# Ethernet2.net
KiCad netlist of a schematic drawn in Altium Designer
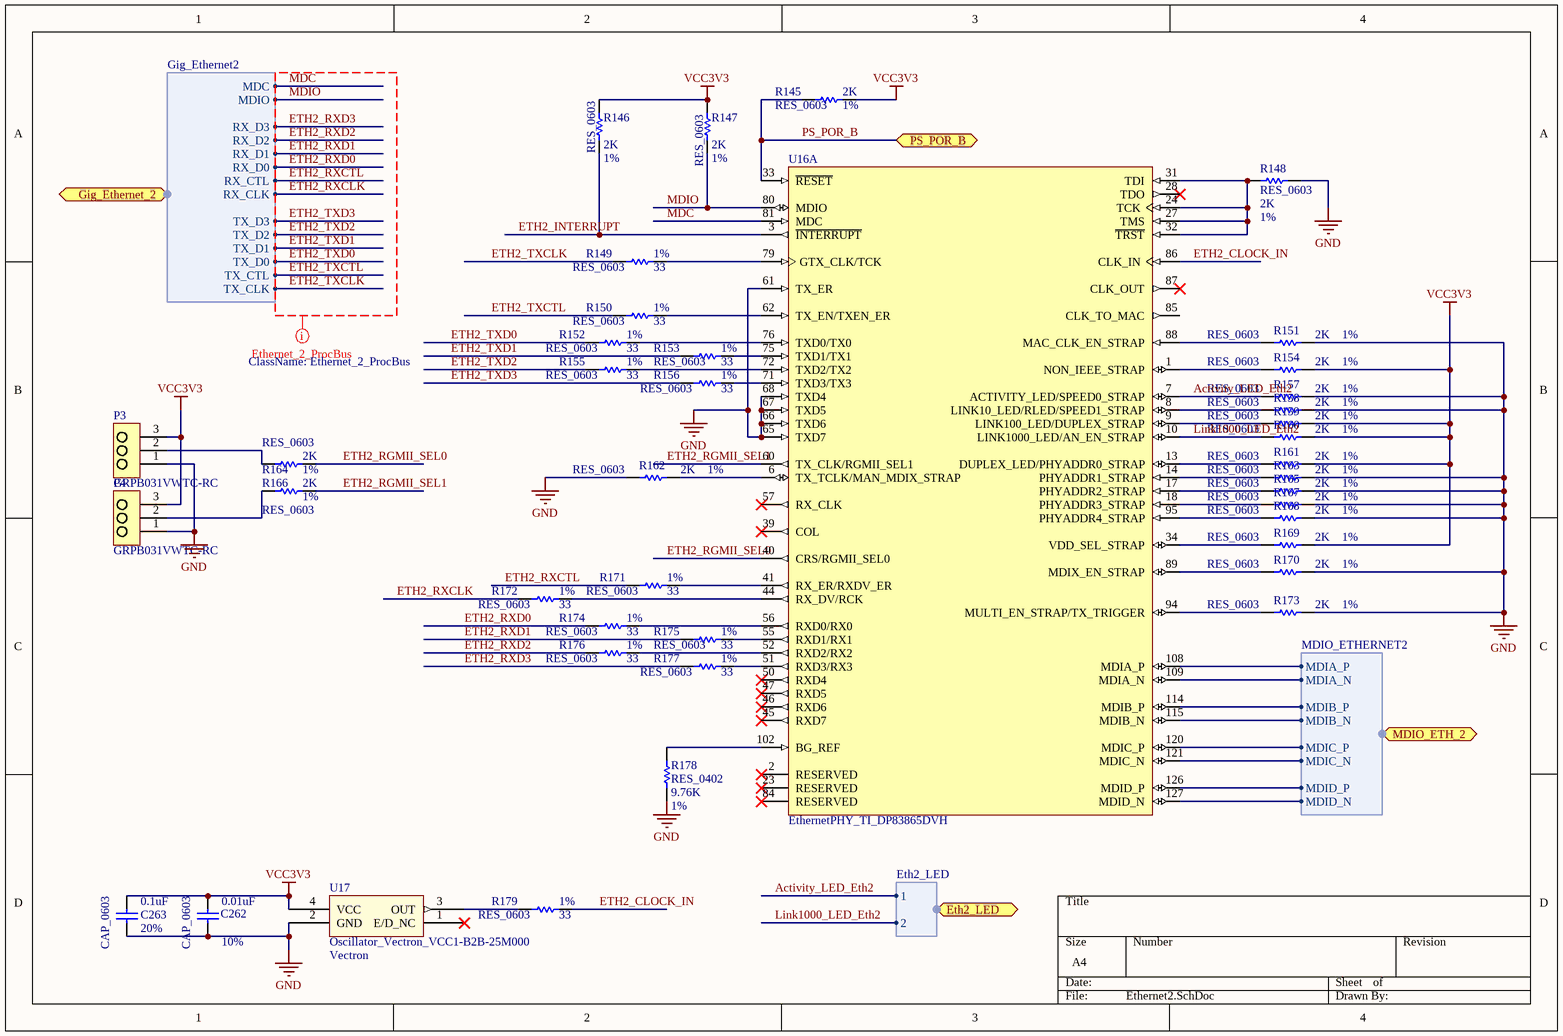
[diagram p0: Ethernet2.SchDoc]

(export (version "E")
  (design (tool "Eeschema 10.0.6"))
  (components
    (comp (ref "C262")
      (value "CAP_0603")
      (footprint "CAPC0603(1608)100_N")
      (description "CAP CER 10000PF 6.3V X7R 0603")
      (fields
        (field (name "ALTIUM_VALUE") "0.01uF")
        (field (name "TOLERANCE") "10%")
        (field (name "PART NUMBER") "C0603C103K9RACTU")
        (field (name "MANUFACTURER") "Kemet")
      )
      (libsource (lib "COMRAD_Database") (part "CAP_0603"))
    )
    (comp (ref "C263")
      (value "CAP_0603")
      (footprint "CAPC0603(1608)100_N")
      (description "CAP CER 0.1UF 6.3V 20% X7R 0603")
      (fields
        (field (name "ALTIUM_VALUE") "0.1uF")
        (field (name "TOLERANCE") "20%")
        (field (name "PART NUMBER") "6R3X14W104MV4T")
        (field (name "MANUFACTURER") "Johanson Dielectrics Inc")
      )
      (libsource (lib "COMRAD_Database") (part "CAP_0603"))
    )
    (comp (ref "P3")
      (value "GRPB031VWTC-RC")
      (footprint "Header_3-Pos_Sullins_GRPB031VWTC-RC")
      (description "CONN HEADER .050\" 3POS SMD GOLD")
      (fields (field (name "MANUFACTURER") "Sullins Connector Solutions"))
      (libsource (lib "COMRAD_Database") (part "Jumper_Header3"))
    )
    (comp (ref "P4")
      (value "GRPB031VWTC-RC")
      (footprint "Header_3-Pos_Sullins_GRPB031VWTC-RC")
      (description "CONN HEADER .050\" 3POS SMD GOLD")
      (fields (field (name "MANUFACTURER") "Sullins Connector Solutions"))
      (libsource (lib "COMRAD_Database") (part "Jumper_Header3"))
    )
    (comp (ref "R145")
      (value "RES_0603")
      (footprint "RESC0603(1608)_N")
      (description "RES 2.00K OHM 1/10W 1% 0603 SMD")
      (fields
        (field (name "ALTIUM_VALUE") "2K")
        (field (name "TOLERANCE") "1%")
        (field (name "PART NUMBER") "ERJ-3EKF2001V")
        (field (name "MANUFACTURER") "Panasonic Electronics Components")
      )
      (libsource (lib "COMRAD_Database") (part "RES_0603"))
    )
    (comp (ref "R146")
      (value "RES_0603")
      (footprint "RESC0603(1608)_N")
      (description "RES 2.00K OHM 1/10W 1% 0603 SMD")
      (fields
        (field (name "ALTIUM_VALUE") "2K")
        (field (name "TOLERANCE") "1%")
        (field (name "PART NUMBER") "ERJ-3EKF2001V")
        (field (name "MANUFACTURER") "Panasonic Electronics Components")
      )
      (libsource (lib "COMRAD_Database") (part "RES_0603"))
    )
    (comp (ref "R147")
      (value "RES_0603")
      (footprint "RESC0603(1608)_N")
      (description "RES 2.00K OHM 1/10W 1% 0603 SMD")
      (fields
        (field (name "ALTIUM_VALUE") "2K")
        (field (name "TOLERANCE") "1%")
        (field (name "PART NUMBER") "ERJ-3EKF2001V")
        (field (name "MANUFACTURER") "Panasonic Electronics Components")
      )
      (libsource (lib "COMRAD_Database") (part "RES_0603"))
    )
    (comp (ref "R148")
      (value "RES_0603")
      (footprint "RESC0603(1608)_N")
      (description "RES 2.00K OHM 1/10W 1% 0603 SMD")
      (fields
        (field (name "ALTIUM_VALUE") "2K")
        (field (name "TOLERANCE") "1%")
        (field (name "PART NUMBER") "ERJ-3EKF2001V")
        (field (name "MANUFACTURER") "Panasonic Electronics Components")
      )
      (libsource (lib "COMRAD_Database") (part "RES_0603"))
    )
    (comp (ref "R149")
      (value "RES_0603")
      (footprint "RESC0603(1608)_N")
      (description "RES 33.0 OHM 1/10W 1% 0603 SMD")
      (fields
        (field (name "ALTIUM_VALUE") "33")
        (field (name "TOLERANCE") "1%")
        (field (name "PART NUMBER") "ERJ-3EKF33R0V")
        (field (name "MANUFACTURER") "Panasonic Electronics Components")
      )
      (libsource (lib "COMRAD_Database") (part "RES_0603"))
    )
    (comp (ref "R150")
      (value "RES_0603")
      (footprint "RESC0603(1608)_N")
      (description "RES 33.0 OHM 1/10W 1% 0603 SMD")
      (fields
        (field (name "ALTIUM_VALUE") "33")
        (field (name "TOLERANCE") "1%")
        (field (name "PART NUMBER") "ERJ-3EKF33R0V")
        (field (name "MANUFACTURER") "Panasonic Electronics Components")
      )
      (libsource (lib "COMRAD_Database") (part "RES_0603"))
    )
    (comp (ref "R151")
      (value "RES_0603")
      (footprint "RESC0603(1608)_N")
      (description "RES 2.00K OHM 1/10W 1% 0603 SMD")
      (fields
        (field (name "ALTIUM_VALUE") "2K")
        (field (name "TOLERANCE") "1%")
        (field (name "PART NUMBER") "ERJ-3EKF2001V")
        (field (name "MANUFACTURER") "Panasonic Electronics Components")
      )
      (libsource (lib "COMRAD_Database") (part "RES_0603"))
    )
    (comp (ref "R152")
      (value "RES_0603")
      (footprint "RESC0603(1608)_N")
      (description "RES 33.0 OHM 1/10W 1% 0603 SMD")
      (fields
        (field (name "ALTIUM_VALUE") "33")
        (field (name "TOLERANCE") "1%")
        (field (name "PART NUMBER") "ERJ-3EKF33R0V")
        (field (name "MANUFACTURER") "Panasonic Electronics Components")
      )
      (libsource (lib "COMRAD_Database") (part "RES_0603"))
    )
    (comp (ref "R153")
      (value "RES_0603")
      (footprint "RESC0603(1608)_N")
      (description "RES 33.0 OHM 1/10W 1% 0603 SMD")
      (fields
        (field (name "ALTIUM_VALUE") "33")
        (field (name "TOLERANCE") "1%")
        (field (name "PART NUMBER") "ERJ-3EKF33R0V")
        (field (name "MANUFACTURER") "Panasonic Electronics Components")
      )
      (libsource (lib "COMRAD_Database") (part "RES_0603"))
    )
    (comp (ref "R154")
      (value "RES_0603")
      (footprint "RESC0603(1608)_N")
      (description "RES 2.00K OHM 1/10W 1% 0603 SMD")
      (fields
        (field (name "ALTIUM_VALUE") "2K")
        (field (name "TOLERANCE") "1%")
        (field (name "PART NUMBER") "ERJ-3EKF2001V")
        (field (name "MANUFACTURER") "Panasonic Electronics Components")
      )
      (libsource (lib "COMRAD_Database") (part "RES_0603"))
    )
    (comp (ref "R155")
      (value "RES_0603")
      (footprint "RESC0603(1608)_N")
      (description "RES 33.0 OHM 1/10W 1% 0603 SMD")
      (fields
        (field (name "ALTIUM_VALUE") "33")
        (field (name "TOLERANCE") "1%")
        (field (name "PART NUMBER") "ERJ-3EKF33R0V")
        (field (name "MANUFACTURER") "Panasonic Electronics Components")
      )
      (libsource (lib "COMRAD_Database") (part "RES_0603"))
    )
    (comp (ref "R156")
      (value "RES_0603")
      (footprint "RESC0603(1608)_N")
      (description "RES 33.0 OHM 1/10W 1% 0603 SMD")
      (fields
        (field (name "ALTIUM_VALUE") "33")
        (field (name "TOLERANCE") "1%")
        (field (name "PART NUMBER") "ERJ-3EKF33R0V")
        (field (name "MANUFACTURER") "Panasonic Electronics Components")
      )
      (libsource (lib "COMRAD_Database") (part "RES_0603"))
    )
    (comp (ref "R157")
      (value "RES_0603")
      (footprint "RESC0603(1608)_N")
      (description "RES 2.00K OHM 1/10W 1% 0603 SMD")
      (fields
        (field (name "ALTIUM_VALUE") "2K")
        (field (name "TOLERANCE") "1%")
        (field (name "PART NUMBER") "ERJ-3EKF2001V")
        (field (name "MANUFACTURER") "Panasonic Electronics Components")
      )
      (libsource (lib "COMRAD_Database") (part "RES_0603"))
    )
    (comp (ref "R158")
      (value "RES_0603")
      (footprint "RESC0603(1608)_N")
      (description "RES 2.00K OHM 1/10W 1% 0603 SMD")
      (fields
        (field (name "ALTIUM_VALUE") "2K")
        (field (name "TOLERANCE") "1%")
        (field (name "PART NUMBER") "ERJ-3EKF2001V")
        (field (name "MANUFACTURER") "Panasonic Electronics Components")
      )
      (libsource (lib "COMRAD_Database") (part "RES_0603"))
    )
    (comp (ref "R159")
      (value "RES_0603")
      (footprint "RESC0603(1608)_N")
      (description "RES 2.00K OHM 1/10W 1% 0603 SMD")
      (fields
        (field (name "ALTIUM_VALUE") "2K")
        (field (name "TOLERANCE") "1%")
        (field (name "PART NUMBER") "ERJ-3EKF2001V")
        (field (name "MANUFACTURER") "Panasonic Electronics Components")
      )
      (libsource (lib "COMRAD_Database") (part "RES_0603"))
    )
    (comp (ref "R160")
      (value "RES_0603")
      (footprint "RESC0603(1608)_N")
      (description "RES 2.00K OHM 1/10W 1% 0603 SMD")
      (fields
        (field (name "ALTIUM_VALUE") "2K")
        (field (name "TOLERANCE") "1%")
        (field (name "PART NUMBER") "ERJ-3EKF2001V")
        (field (name "MANUFACTURER") "Panasonic Electronics Components")
      )
      (libsource (lib "COMRAD_Database") (part "RES_0603"))
    )
    (comp (ref "R161")
      (value "RES_0603")
      (footprint "RESC0603(1608)_N")
      (description "RES 2.00K OHM 1/10W 1% 0603 SMD")
      (fields
        (field (name "ALTIUM_VALUE") "2K")
        (field (name "TOLERANCE") "1%")
        (field (name "PART NUMBER") "ERJ-3EKF2001V")
        (field (name "MANUFACTURER") "Panasonic Electronics Components")
      )
      (libsource (lib "COMRAD_Database") (part "RES_0603"))
    )
    (comp (ref "R162")
      (value "RES_0603")
      (footprint "RESC0603(1608)_N")
      (description "RES 2.00K OHM 1/10W 1% 0603 SMD")
      (fields
        (field (name "ALTIUM_VALUE") "2K")
        (field (name "TOLERANCE") "1%")
        (field (name "PART NUMBER") "ERJ-3EKF2001V")
        (field (name "MANUFACTURER") "Panasonic Electronics Components")
      )
      (libsource (lib "COMRAD_Database") (part "RES_0603"))
    )
    (comp (ref "R163")
      (value "RES_0603")
      (footprint "RESC0603(1608)_N")
      (description "RES 2.00K OHM 1/10W 1% 0603 SMD")
      (fields
        (field (name "ALTIUM_VALUE") "2K")
        (field (name "TOLERANCE") "1%")
        (field (name "PART NUMBER") "ERJ-3EKF2001V")
        (field (name "MANUFACTURER") "Panasonic Electronics Components")
      )
      (libsource (lib "COMRAD_Database") (part "RES_0603"))
    )
    (comp (ref "R164")
      (value "RES_0603")
      (footprint "RESC0603(1608)_N")
      (description "RES 2.00K OHM 1/10W 1% 0603 SMD")
      (fields
        (field (name "ALTIUM_VALUE") "2K")
        (field (name "TOLERANCE") "1%")
        (field (name "PART NUMBER") "ERJ-3EKF2001V")
        (field (name "MANUFACTURER") "Panasonic Electronics Components")
      )
      (libsource (lib "COMRAD_Database") (part "RES_0603"))
    )
    (comp (ref "R165")
      (value "RES_0603")
      (footprint "RESC0603(1608)_N")
      (description "RES 2.00K OHM 1/10W 1% 0603 SMD")
      (fields
        (field (name "ALTIUM_VALUE") "2K")
        (field (name "TOLERANCE") "1%")
        (field (name "PART NUMBER") "ERJ-3EKF2001V")
        (field (name "MANUFACTURER") "Panasonic Electronics Components")
      )
      (libsource (lib "COMRAD_Database") (part "RES_0603"))
    )
    (comp (ref "R166")
      (value "RES_0603")
      (footprint "RESC0603(1608)_N")
      (description "RES 2.00K OHM 1/10W 1% 0603 SMD")
      (fields
        (field (name "ALTIUM_VALUE") "2K")
        (field (name "TOLERANCE") "1%")
        (field (name "PART NUMBER") "ERJ-3EKF2001V")
        (field (name "MANUFACTURER") "Panasonic Electronics Components")
      )
      (libsource (lib "COMRAD_Database") (part "RES_0603"))
    )
    (comp (ref "R167")
      (value "RES_0603")
      (footprint "RESC0603(1608)_N")
      (description "RES 2.00K OHM 1/10W 1% 0603 SMD")
      (fields
        (field (name "ALTIUM_VALUE") "2K")
        (field (name "TOLERANCE") "1%")
        (field (name "PART NUMBER") "ERJ-3EKF2001V")
        (field (name "MANUFACTURER") "Panasonic Electronics Components")
      )
      (libsource (lib "COMRAD_Database") (part "RES_0603"))
    )
    (comp (ref "R168")
      (value "RES_0603")
      (footprint "RESC0603(1608)_N")
      (description "RES 2.00K OHM 1/10W 1% 0603 SMD")
      (fields
        (field (name "ALTIUM_VALUE") "2K")
        (field (name "TOLERANCE") "1%")
        (field (name "PART NUMBER") "ERJ-3EKF2001V")
        (field (name "MANUFACTURER") "Panasonic Electronics Components")
      )
      (libsource (lib "COMRAD_Database") (part "RES_0603"))
    )
    (comp (ref "R169")
      (value "RES_0603")
      (footprint "RESC0603(1608)_N")
      (description "RES 2.00K OHM 1/10W 1% 0603 SMD")
      (fields
        (field (name "ALTIUM_VALUE") "2K")
        (field (name "TOLERANCE") "1%")
        (field (name "PART NUMBER") "ERJ-3EKF2001V")
        (field (name "MANUFACTURER") "Panasonic Electronics Components")
      )
      (libsource (lib "COMRAD_Database") (part "RES_0603"))
    )
    (comp (ref "R170")
      (value "RES_0603")
      (footprint "RESC0603(1608)_N")
      (description "RES 2.00K OHM 1/10W 1% 0603 SMD")
      (fields
        (field (name "ALTIUM_VALUE") "2K")
        (field (name "TOLERANCE") "1%")
        (field (name "PART NUMBER") "ERJ-3EKF2001V")
        (field (name "MANUFACTURER") "Panasonic Electronics Components")
      )
      (libsource (lib "COMRAD_Database") (part "RES_0603"))
    )
    (comp (ref "R171")
      (value "RES_0603")
      (footprint "RESC0603(1608)_N")
      (description "RES 33.0 OHM 1/10W 1% 0603 SMD")
      (fields
        (field (name "ALTIUM_VALUE") "33")
        (field (name "TOLERANCE") "1%")
        (field (name "PART NUMBER") "ERJ-3EKF33R0V")
        (field (name "MANUFACTURER") "Panasonic Electronics Components")
      )
      (libsource (lib "COMRAD_Database") (part "RES_0603"))
    )
    (comp (ref "R172")
      (value "RES_0603")
      (footprint "RESC0603(1608)_N")
      (description "RES 33.0 OHM 1/10W 1% 0603 SMD")
      (fields
        (field (name "ALTIUM_VALUE") "33")
        (field (name "TOLERANCE") "1%")
        (field (name "PART NUMBER") "ERJ-3EKF33R0V")
        (field (name "MANUFACTURER") "Panasonic Electronics Components")
      )
      (libsource (lib "COMRAD_Database") (part "RES_0603"))
    )
    (comp (ref "R173")
      (value "RES_0603")
      (footprint "RESC0603(1608)_N")
      (description "RES 2.00K OHM 1/10W 1% 0603 SMD")
      (fields
        (field (name "ALTIUM_VALUE") "2K")
        (field (name "TOLERANCE") "1%")
        (field (name "PART NUMBER") "ERJ-3EKF2001V")
        (field (name "MANUFACTURER") "Panasonic Electronics Components")
      )
      (libsource (lib "COMRAD_Database") (part "RES_0603"))
    )
    (comp (ref "R174")
      (value "RES_0603")
      (footprint "RESC0603(1608)_N")
      (description "RES 33.0 OHM 1/10W 1% 0603 SMD")
      (fields
        (field (name "ALTIUM_VALUE") "33")
        (field (name "TOLERANCE") "1%")
        (field (name "PART NUMBER") "ERJ-3EKF33R0V")
        (field (name "MANUFACTURER") "Panasonic Electronics Components")
      )
      (libsource (lib "COMRAD_Database") (part "RES_0603"))
    )
    (comp (ref "R175")
      (value "RES_0603")
      (footprint "RESC0603(1608)_N")
      (description "RES 33.0 OHM 1/10W 1% 0603 SMD")
      (fields
        (field (name "ALTIUM_VALUE") "33")
        (field (name "TOLERANCE") "1%")
        (field (name "PART NUMBER") "ERJ-3EKF33R0V")
        (field (name "MANUFACTURER") "Panasonic Electronics Components")
      )
      (libsource (lib "COMRAD_Database") (part "RES_0603"))
    )
    (comp (ref "R176")
      (value "RES_0603")
      (footprint "RESC0603(1608)_N")
      (description "RES 33.0 OHM 1/10W 1% 0603 SMD")
      (fields
        (field (name "ALTIUM_VALUE") "33")
        (field (name "TOLERANCE") "1%")
        (field (name "PART NUMBER") "ERJ-3EKF33R0V")
        (field (name "MANUFACTURER") "Panasonic Electronics Components")
      )
      (libsource (lib "COMRAD_Database") (part "RES_0603"))
    )
    (comp (ref "R177")
      (value "RES_0603")
      (footprint "RESC0603(1608)_N")
      (description "RES 33.0 OHM 1/10W 1% 0603 SMD")
      (fields
        (field (name "ALTIUM_VALUE") "33")
        (field (name "TOLERANCE") "1%")
        (field (name "PART NUMBER") "ERJ-3EKF33R0V")
        (field (name "MANUFACTURER") "Panasonic Electronics Components")
      )
      (libsource (lib "COMRAD_Database") (part "RES_0603"))
    )
    (comp (ref "R178")
      (value "RES_0402")
      (footprint "RESC0402(1005)_N")
      (description "9.76K ohm, 1% 1/16W, 0402")
      (fields
        (field (name "ALTIUM_VALUE") "9.76K")
        (field (name "TOLERANCE") "1%")
        (field (name "PART NUMBER") "CRCW04029K76FKED")
        (field (name "MANUFACTURER") "Vishay/Dale")
      )
      (libsource (lib "COMRAD_Database") (part "RES_0402"))
    )
    (comp (ref "R179")
      (value "RES_0603")
      (footprint "RESC0603(1608)_N")
      (description "RES 33.0 OHM 1/10W 1% 0603 SMD")
      (fields
        (field (name "ALTIUM_VALUE") "33")
        (field (name "TOLERANCE") "1%")
        (field (name "PART NUMBER") "ERJ-3EKF33R0V")
        (field (name "MANUFACTURER") "Panasonic Electronics Components")
      )
      (libsource (lib "COMRAD_Database") (part "RES_0603"))
    )
    (comp (ref "U16")
      (value "EthernetPHY_TI_DP83865DVH")
      (footprint "EthernetPHY_TI_DP83865(PQFP)_VLA128A_N")
      (description "Ethernet PHY_TI_DP83865DVH, Gigabit Ethernet PHYTER,128 Lead Plastic Flat Pack")
      (fields (field (name "PART NUMBER") "DP83865DVH") (field (name "MANUFACTURER") "Texas Instruments"))
      (libsource (lib "COMRAD_Database") (part "EthernetPHY_TI_DP83865DVH"))
    )
    (comp (ref "U17")
      (value "Oscillator_Vectron_VCC1-B2B-25M000")
      (footprint "Oscillator_Vectron_VCC1-B2B-25M000_SMD")
      (description "VCC1-B2B-25M000, 25MHz, 3.3V +/- 10%, No tri-state, +/-50 ppm, -40 to +85 deg")
      (fields (field (name "PART NUMBER") "VCC1-B2B-25M000") (field (name "MANUFACTURER") "Vectron"))
      (libsource (lib "COMRAD_Database") (part "Oscillator_Vectron_VCC1-B2B-25M000"))
    )
  )
  (nets
    (net (code "4") (name "/Activity_LED_Eth2") (class "Default")
      (node (ref "R157") (pin "2") (pinfunction "2_2") (pintype "passive"))
      (node (ref "U16") (pin "7") (pinfunction "ACTIVITY_LED/SPEED0_STRAP_7") (pintype "bidirectional"))
    )
    (net (code "5") (name "/ETH2_CLOCK_IN") (class "Default")
      (node (ref "R179") (pin "2") (pinfunction "2_2") (pintype "passive"))
      (node (ref "U16") (pin "86") (pinfunction "CLK_IN_86") (pintype "input"))
    )
    (net (code "6") (name "/ETH2_INTERRUPT") (class "Default")
      (node (ref "R146") (pin "1") (pinfunction "1_1") (pintype "passive"))
      (node (ref "U16") (pin "3") (pinfunction "~{INTERRUPT}_3") (pintype "output"))
    )
    (net (code "7") (name "/ETH2_RGMII_SEL0") (class "Default")
      (node (ref "R164") (pin "1") (pinfunction "1_1") (pintype "passive"))
      (node (ref "U16") (pin "40") (pinfunction "CRS/RGMII_SEL0_40") (pintype "output"))
    )
    (net (code "8") (name "/ETH2_RGMII_SEL1") (class "Default")
      (node (ref "R166") (pin "1") (pinfunction "1_1") (pintype "passive"))
      (node (ref "U16") (pin "60") (pinfunction "TX_CLK/RGMII_SEL1_60") (pintype "output"))
    )
    (net (code "9") (name "/ETH2_RXCLK") (class "Default")
      (node (ref "R172") (pin "1") (pinfunction "1_1") (pintype "passive"))
    )
    (net (code "10") (name "/ETH2_RXCTL") (class "Default")
      (node (ref "R171") (pin "1") (pinfunction "1_1") (pintype "passive"))
    )
    (net (code "11") (name "/ETH2_RXD0") (class "Default")
      (node (ref "R174") (pin "1") (pinfunction "1_1") (pintype "passive"))
    )
    (net (code "12") (name "/ETH2_RXD1") (class "Default")
      (node (ref "R175") (pin "1") (pinfunction "1_1") (pintype "passive"))
    )
    (net (code "13") (name "/ETH2_RXD2") (class "Default")
      (node (ref "R176") (pin "1") (pinfunction "1_1") (pintype "passive"))
    )
    (net (code "14") (name "/ETH2_RXD3") (class "Default")
      (node (ref "R177") (pin "1") (pinfunction "1_1") (pintype "passive"))
    )
    (net (code "15") (name "/ETH2_TXCLK") (class "Default")
      (node (ref "R149") (pin "1") (pinfunction "1_1") (pintype "passive"))
    )
    (net (code "16") (name "/ETH2_TXCTL") (class "Default")
      (node (ref "R150") (pin "1") (pinfunction "1_1") (pintype "passive"))
    )
    (net (code "17") (name "/ETH2_TXD0") (class "Default")
      (node (ref "R152") (pin "1") (pinfunction "1_1") (pintype "passive"))
    )
    (net (code "18") (name "/ETH2_TXD1") (class "Default")
      (node (ref "R153") (pin "1") (pinfunction "1_1") (pintype "passive"))
    )
    (net (code "19") (name "/ETH2_TXD2") (class "Default")
      (node (ref "R155") (pin "1") (pinfunction "1_1") (pintype "passive"))
    )
    (net (code "20") (name "/ETH2_TXD3") (class "Default")
      (node (ref "R156") (pin "1") (pinfunction "1_1") (pintype "passive"))
    )
    (net (code "21") (name "/Link1000_LED_Eth2") (class "Default")
      (node (ref "R160") (pin "2") (pinfunction "2_2") (pintype "passive"))
      (node (ref "U16") (pin "10") (pinfunction "LINK1000_LED/AN_EN_STRAP_10") (pintype "bidirectional"))
    )
    (net (code "22") (name "/MDC") (class "Default")
      (node (ref "U16") (pin "81") (pinfunction "MDC_81") (pintype "input"))
    )
    (net (code "23") (name "/MDIA_N") (class "Default")
      (node (ref "U16") (pin "109") (pinfunction "MDIA_N_109") (pintype "bidirectional"))
    )
    (net (code "24") (name "/MDIA_P") (class "Default")
      (node (ref "U16") (pin "108") (pinfunction "MDIA_P_108") (pintype "bidirectional"))
    )
    (net (code "25") (name "/MDIB_N") (class "Default")
      (node (ref "U16") (pin "115") (pinfunction "MDIB_N_115") (pintype "bidirectional"))
    )
    (net (code "26") (name "/MDIB_P") (class "Default")
      (node (ref "U16") (pin "114") (pinfunction "MDIB_P_114") (pintype "bidirectional"))
    )
    (net (code "27") (name "/MDIC_N") (class "Default")
      (node (ref "U16") (pin "121") (pinfunction "MDIC_N_121") (pintype "bidirectional"))
    )
    (net (code "28") (name "/MDIC_P") (class "Default")
      (node (ref "U16") (pin "120") (pinfunction "MDIC_P_120") (pintype "bidirectional"))
    )
    (net (code "29") (name "/MDID_N") (class "Default")
      (node (ref "U16") (pin "127") (pinfunction "MDID_N_127") (pintype "bidirectional"))
    )
    (net (code "30") (name "/MDID_P") (class "Default")
      (node (ref "U16") (pin "126") (pinfunction "MDID_P_126") (pintype "bidirectional"))
    )
    (net (code "31") (name "/MDIO") (class "Default")
      (node (ref "R147") (pin "1") (pinfunction "1_1") (pintype "passive"))
      (node (ref "U16") (pin "80") (pinfunction "MDIO_80") (pintype "bidirectional"))
    )
    (net (code "32") (name "/PS_POR_B") (class "Default")
      (node (ref "R145") (pin "2") (pinfunction "2_2") (pintype "passive"))
      (node (ref "U16") (pin "33") (pinfunction "~{RESET}_33") (pintype "input"))
    )
    (net (code "36") (name "GND") (class "Default")
      (node (ref "C262") (pin "1") (pinfunction "1_1") (pintype "passive"))
      (node (ref "C263") (pin "2") (pinfunction "2_2") (pintype "passive"))
      (node (ref "P3") (pin "1") (pinfunction "1_1") (pintype "passive"))
      (node (ref "P4") (pin "1") (pinfunction "1_1") (pintype "passive"))
      (node (ref "R148") (pin "1") (pinfunction "1_1") (pintype "passive"))
      (node (ref "R151") (pin "1") (pinfunction "1_1") (pintype "passive"))
      (node (ref "R157") (pin "1") (pinfunction "1_1") (pintype "passive"))
      (node (ref "R158") (pin "1") (pinfunction "1_1") (pintype "passive"))
      (node (ref "R162") (pin "2") (pinfunction "2_2") (pintype "passive"))
      (node (ref "R163") (pin "1") (pinfunction "1_1") (pintype "passive"))
      (node (ref "R165") (pin "1") (pinfunction "1_1") (pintype "passive"))
      (node (ref "R167") (pin "1") (pinfunction "1_1") (pintype "passive"))
      (node (ref "R168") (pin "1") (pinfunction "1_1") (pintype "passive"))
      (node (ref "R170") (pin "1") (pinfunction "1_1") (pintype "passive"))
      (node (ref "R173") (pin "1") (pinfunction "1_1") (pintype "passive"))
      (node (ref "R178") (pin "1") (pinfunction "1_1") (pintype "passive"))
      (node (ref "U16") (pin "61") (pinfunction "TX_ER_61") (pintype "input"))
      (node (ref "U16") (pin "65") (pinfunction "TXD7_65") (pintype "input"))
      (node (ref "U16") (pin "66") (pinfunction "TXD6_66") (pintype "input"))
      (node (ref "U16") (pin "67") (pinfunction "TXD5_67") (pintype "input"))
      (node (ref "U16") (pin "68") (pinfunction "TXD4_68") (pintype "input"))
      (node (ref "U17") (pin "2") (pinfunction "GND_2") (pintype "power_in"))
    )
    (net (code "37") (name "Net-(P3-Pad2)") (class "Default")
      (node (ref "P3") (pin "2") (pinfunction "2_2") (pintype "passive"))
      (node (ref "R164") (pin "2") (pinfunction "2_2") (pintype "passive"))
    )
    (net (code "38") (name "Net-(P4-Pad2)") (class "Default")
      (node (ref "P4") (pin "2") (pinfunction "2_2") (pintype "passive"))
      (node (ref "R166") (pin "2") (pinfunction "2_2") (pintype "passive"))
    )
    (net (code "39") (name "Net-(U16A-BG_REF)") (class "Default")
      (node (ref "R178") (pin "2") (pinfunction "2_2") (pintype "passive"))
      (node (ref "U16") (pin "102") (pinfunction "BG_REF_102") (pintype "input"))
    )
    (net (code "40") (name "Net-(U16A-DUPLEX_LED{slash}PHYADDR0_STRAP)") (class "Default")
      (node (ref "R161") (pin "2") (pinfunction "2_2") (pintype "passive"))
      (node (ref "U16") (pin "13") (pinfunction "DUPLEX_LED/PHYADDR0_STRAP_13") (pintype "bidirectional"))
    )
    (net (code "41") (name "Net-(U16A-GTX_CLK{slash}TCK)") (class "Default")
      (node (ref "R149") (pin "2") (pinfunction "2_2") (pintype "passive"))
      (node (ref "U16") (pin "79") (pinfunction "GTX_CLK/TCK_79") (pintype "input"))
    )
    (net (code "42") (name "Net-(U16A-LINK10_LED{slash}RLED{slash}SPEED1_STRAP)") (class "Default")
      (node (ref "R158") (pin "2") (pinfunction "2_2") (pintype "passive"))
      (node (ref "U16") (pin "8") (pinfunction "LINK10_LED/RLED/SPEED1_STRAP_8") (pintype "bidirectional"))
    )
    (net (code "43") (name "Net-(U16A-LINK100_LED{slash}DUPLEX_STRAP)") (class "Default")
      (node (ref "R159") (pin "2") (pinfunction "2_2") (pintype "passive"))
      (node (ref "U16") (pin "9") (pinfunction "LINK100_LED/DUPLEX_STRAP_9") (pintype "bidirectional"))
    )
    (net (code "44") (name "Net-(U16A-MAC_CLK_EN_STRAP)") (class "Default")
      (node (ref "R151") (pin "2") (pinfunction "2_2") (pintype "passive"))
      (node (ref "U16") (pin "88") (pinfunction "MAC_CLK_EN_STRAP_88") (pintype "input"))
    )
    (net (code "45") (name "Net-(U16A-MDIX_EN_STRAP)") (class "Default")
      (node (ref "R170") (pin "2") (pinfunction "2_2") (pintype "passive"))
      (node (ref "U16") (pin "89") (pinfunction "MDIX_EN_STRAP_89") (pintype "bidirectional"))
    )
    (net (code "46") (name "Net-(U16A-MULTI_EN_STRAP{slash}TX_TRIGGER)") (class "Default")
      (node (ref "R173") (pin "2") (pinfunction "2_2") (pintype "passive"))
      (node (ref "U16") (pin "94") (pinfunction "MULTI_EN_STRAP/TX_TRIGGER_94") (pintype "bidirectional"))
    )
    (net (code "47") (name "Net-(U16A-NON_IEEE_STRAP)") (class "Default")
      (node (ref "R154") (pin "2") (pinfunction "2_2") (pintype "passive"))
      (node (ref "U16") (pin "1") (pinfunction "NON_IEEE_STRAP_1") (pintype "bidirectional"))
    )
    (net (code "48") (name "Net-(U16A-PHYADDR1_STRAP)") (class "Default")
      (node (ref "R163") (pin "2") (pinfunction "2_2") (pintype "passive"))
      (node (ref "U16") (pin "14") (pinfunction "PHYADDR1_STRAP_14") (pintype "input"))
    )
    (net (code "49") (name "Net-(U16A-PHYADDR2_STRAP)") (class "Default")
      (node (ref "R165") (pin "2") (pinfunction "2_2") (pintype "passive"))
      (node (ref "U16") (pin "17") (pinfunction "PHYADDR2_STRAP_17") (pintype "input"))
    )
    (net (code "50") (name "Net-(U16A-PHYADDR3_STRAP)") (class "Default")
      (node (ref "R167") (pin "2") (pinfunction "2_2") (pintype "passive"))
      (node (ref "U16") (pin "18") (pinfunction "PHYADDR3_STRAP_18") (pintype "input"))
    )
    (net (code "51") (name "Net-(U16A-PHYADDR4_STRAP)") (class "Default")
      (node (ref "R168") (pin "2") (pinfunction "2_2") (pintype "passive"))
      (node (ref "U16") (pin "95") (pinfunction "PHYADDR4_STRAP_95") (pintype "input"))
    )
    (net (code "52") (name "Net-(U16A-RXD0{slash}RX0)") (class "Default")
      (node (ref "R174") (pin "2") (pinfunction "2_2") (pintype "passive"))
      (node (ref "U16") (pin "56") (pinfunction "RXD0/RX0_56") (pintype "output"))
    )
    (net (code "53") (name "Net-(U16A-RXD1{slash}RX1)") (class "Default")
      (node (ref "R175") (pin "2") (pinfunction "2_2") (pintype "passive"))
      (node (ref "U16") (pin "55") (pinfunction "RXD1/RX1_55") (pintype "output"))
    )
    (net (code "54") (name "Net-(U16A-RXD2{slash}RX2)") (class "Default")
      (node (ref "R176") (pin "2") (pinfunction "2_2") (pintype "passive"))
      (node (ref "U16") (pin "52") (pinfunction "RXD2/RX2_52") (pintype "output"))
    )
    (net (code "55") (name "Net-(U16A-RXD3{slash}RX3)") (class "Default")
      (node (ref "R177") (pin "2") (pinfunction "2_2") (pintype "passive"))
      (node (ref "U16") (pin "51") (pinfunction "RXD3/RX3_51") (pintype "output"))
    )
    (net (code "56") (name "Net-(U16A-RX_DV{slash}RCK)") (class "Default")
      (node (ref "R172") (pin "2") (pinfunction "2_2") (pintype "passive"))
      (node (ref "U16") (pin "44") (pinfunction "RX_DV/RCK_44") (pintype "output"))
    )
    (net (code "57") (name "Net-(U16A-RX_ER{slash}RXDV_ER)") (class "Default")
      (node (ref "R171") (pin "2") (pinfunction "2_2") (pintype "passive"))
      (node (ref "U16") (pin "41") (pinfunction "RX_ER/RXDV_ER_41") (pintype "output"))
    )
    (net (code "58") (name "Net-(U16A-TCK)") (class "Default")
      (node (ref "R148") (pin "2") (pinfunction "2_2") (pintype "passive"))
      (node (ref "U16") (pin "24") (pinfunction "TCK_24") (pintype "input"))
      (node (ref "U16") (pin "27") (pinfunction "TMS_27") (pintype "input"))
      (node (ref "U16") (pin "31") (pinfunction "TDI_31") (pintype "input"))
      (node (ref "U16") (pin "32") (pinfunction "~{TRST}_32") (pintype "input"))
    )
    (net (code "59") (name "Net-(U16A-TXD0{slash}TX0)") (class "Default")
      (node (ref "R152") (pin "2") (pinfunction "2_2") (pintype "passive"))
      (node (ref "U16") (pin "76") (pinfunction "TXD0/TX0_76") (pintype "input"))
    )
    (net (code "60") (name "Net-(U16A-TXD1{slash}TX1)") (class "Default")
      (node (ref "R153") (pin "2") (pinfunction "2_2") (pintype "passive"))
      (node (ref "U16") (pin "75") (pinfunction "TXD1/TX1_75") (pintype "input"))
    )
    (net (code "61") (name "Net-(U16A-TXD2{slash}TX2)") (class "Default")
      (node (ref "R155") (pin "2") (pinfunction "2_2") (pintype "passive"))
      (node (ref "U16") (pin "72") (pinfunction "TXD2/TX2_72") (pintype "input"))
    )
    (net (code "62") (name "Net-(U16A-TXD3{slash}TX3)") (class "Default")
      (node (ref "R156") (pin "2") (pinfunction "2_2") (pintype "passive"))
      (node (ref "U16") (pin "71") (pinfunction "TXD3/TX3_71") (pintype "input"))
    )
    (net (code "63") (name "Net-(U16A-TX_EN{slash}TXEN_ER)") (class "Default")
      (node (ref "R150") (pin "2") (pinfunction "2_2") (pintype "passive"))
      (node (ref "U16") (pin "62") (pinfunction "TX_EN/TXEN_ER_62") (pintype "input"))
    )
    (net (code "64") (name "Net-(U16A-TX_TCLK{slash}MAN_MDIX_STRAP)") (class "Default")
      (node (ref "R162") (pin "1") (pinfunction "1_1") (pintype "passive"))
      (node (ref "U16") (pin "6") (pinfunction "TX_TCLK/MAN_MDIX_STRAP_6") (pintype "bidirectional"))
    )
    (net (code "65") (name "Net-(U16A-VDD_SEL_STRAP)") (class "Default")
      (node (ref "R169") (pin "2") (pinfunction "2_2") (pintype "passive"))
      (node (ref "U16") (pin "34") (pinfunction "VDD_SEL_STRAP_34") (pintype "bidirectional"))
    )
    (net (code "66") (name "Net-(U17-OUT)") (class "Default")
      (node (ref "R179") (pin "1") (pinfunction "1_1") (pintype "passive"))
      (node (ref "U17") (pin "3") (pinfunction "OUT_3") (pintype "output"))
    )
    (net (code "67") (name "VCC3V3") (class "Default")
      (node (ref "C262") (pin "2") (pinfunction "2_2") (pintype "passive"))
      (node (ref "C263") (pin "1") (pinfunction "1_1") (pintype "passive"))
      (node (ref "P3") (pin "3") (pinfunction "3_3") (pintype "passive"))
      (node (ref "P4") (pin "3") (pinfunction "3_3") (pintype "passive"))
      (node (ref "R145") (pin "1") (pinfunction "1_1") (pintype "passive"))
      (node (ref "R146") (pin "2") (pinfunction "2_2") (pintype "passive"))
      (node (ref "R147") (pin "2") (pinfunction "2_2") (pintype "passive"))
      (node (ref "R154") (pin "1") (pinfunction "1_1") (pintype "passive"))
      (node (ref "R159") (pin "1") (pinfunction "1_1") (pintype "passive"))
      (node (ref "R160") (pin "1") (pinfunction "1_1") (pintype "passive"))
      (node (ref "R161") (pin "1") (pinfunction "1_1") (pintype "passive"))
      (node (ref "R169") (pin "1") (pinfunction "1_1") (pintype "passive"))
      (node (ref "U17") (pin "4") (pinfunction "VCC_4") (pintype "power_in"))
    )
    (net (code "68") (name "unconnected-(U16A-CLK_OUT-Pad87)") (class "Default")
      (node (ref "U16") (pin "87") (pinfunction "CLK_OUT_87") (pintype "output+no_connect"))
    )
    (net (code "69") (name "unconnected-(U16A-CLK_TO_MAC-Pad85)") (class "Default")
      (node (ref "U16") (pin "85") (pinfunction "CLK_TO_MAC_85") (pintype "output"))
    )
    (net (code "70") (name "unconnected-(U16A-COL-Pad39)") (class "Default")
      (node (ref "U16") (pin "39") (pinfunction "COL_39") (pintype "output+no_connect"))
    )
    (net (code "71") (name "unconnected-(U16A-RESERVED-Pad2)") (class "Default")
      (node (ref "U16") (pin "2") (pinfunction "RESERVED_2") (pintype "passive+no_connect"))
    )
    (net (code "72") (name "unconnected-(U16A-RESERVED-Pad23)") (class "Default")
      (node (ref "U16") (pin "23") (pinfunction "RESERVED_23") (pintype "passive+no_connect"))
    )
    (net (code "73") (name "unconnected-(U16A-RESERVED-Pad84)") (class "Default")
      (node (ref "U16") (pin "84") (pinfunction "RESERVED_84") (pintype "passive+no_connect"))
    )
    (net (code "74") (name "unconnected-(U16A-RXD4-Pad50)") (class "Default")
      (node (ref "U16") (pin "50") (pinfunction "RXD4_50") (pintype "output+no_connect"))
    )
    (net (code "75") (name "unconnected-(U16A-RXD5-Pad47)") (class "Default")
      (node (ref "U16") (pin "47") (pinfunction "RXD5_47") (pintype "output+no_connect"))
    )
    (net (code "76") (name "unconnected-(U16A-RXD6-Pad46)") (class "Default")
      (node (ref "U16") (pin "46") (pinfunction "RXD6_46") (pintype "output+no_connect"))
    )
    (net (code "77") (name "unconnected-(U16A-RXD7-Pad45)") (class "Default")
      (node (ref "U16") (pin "45") (pinfunction "RXD7_45") (pintype "output+no_connect"))
    )
    (net (code "78") (name "unconnected-(U16A-RX_CLK-Pad57)") (class "Default")
      (node (ref "U16") (pin "57") (pinfunction "RX_CLK_57") (pintype "output+no_connect"))
    )
    (net (code "79") (name "unconnected-(U16A-TDO-Pad28)") (class "Default")
      (node (ref "U16") (pin "28") (pinfunction "TDO_28") (pintype "output+no_connect"))
    )
    (net (code "80") (name "unconnected-(U17-E{slash}D_NC-Pad1)") (class "Default")
      (node (ref "U17") (pin "1") (pinfunction "E/D_NC_1") (pintype "passive+no_connect"))
    )
  )
)
